# SCH_Eda_Start_2021-09-03.net
KiCad netlist of a schematic drawn in EasyEDA
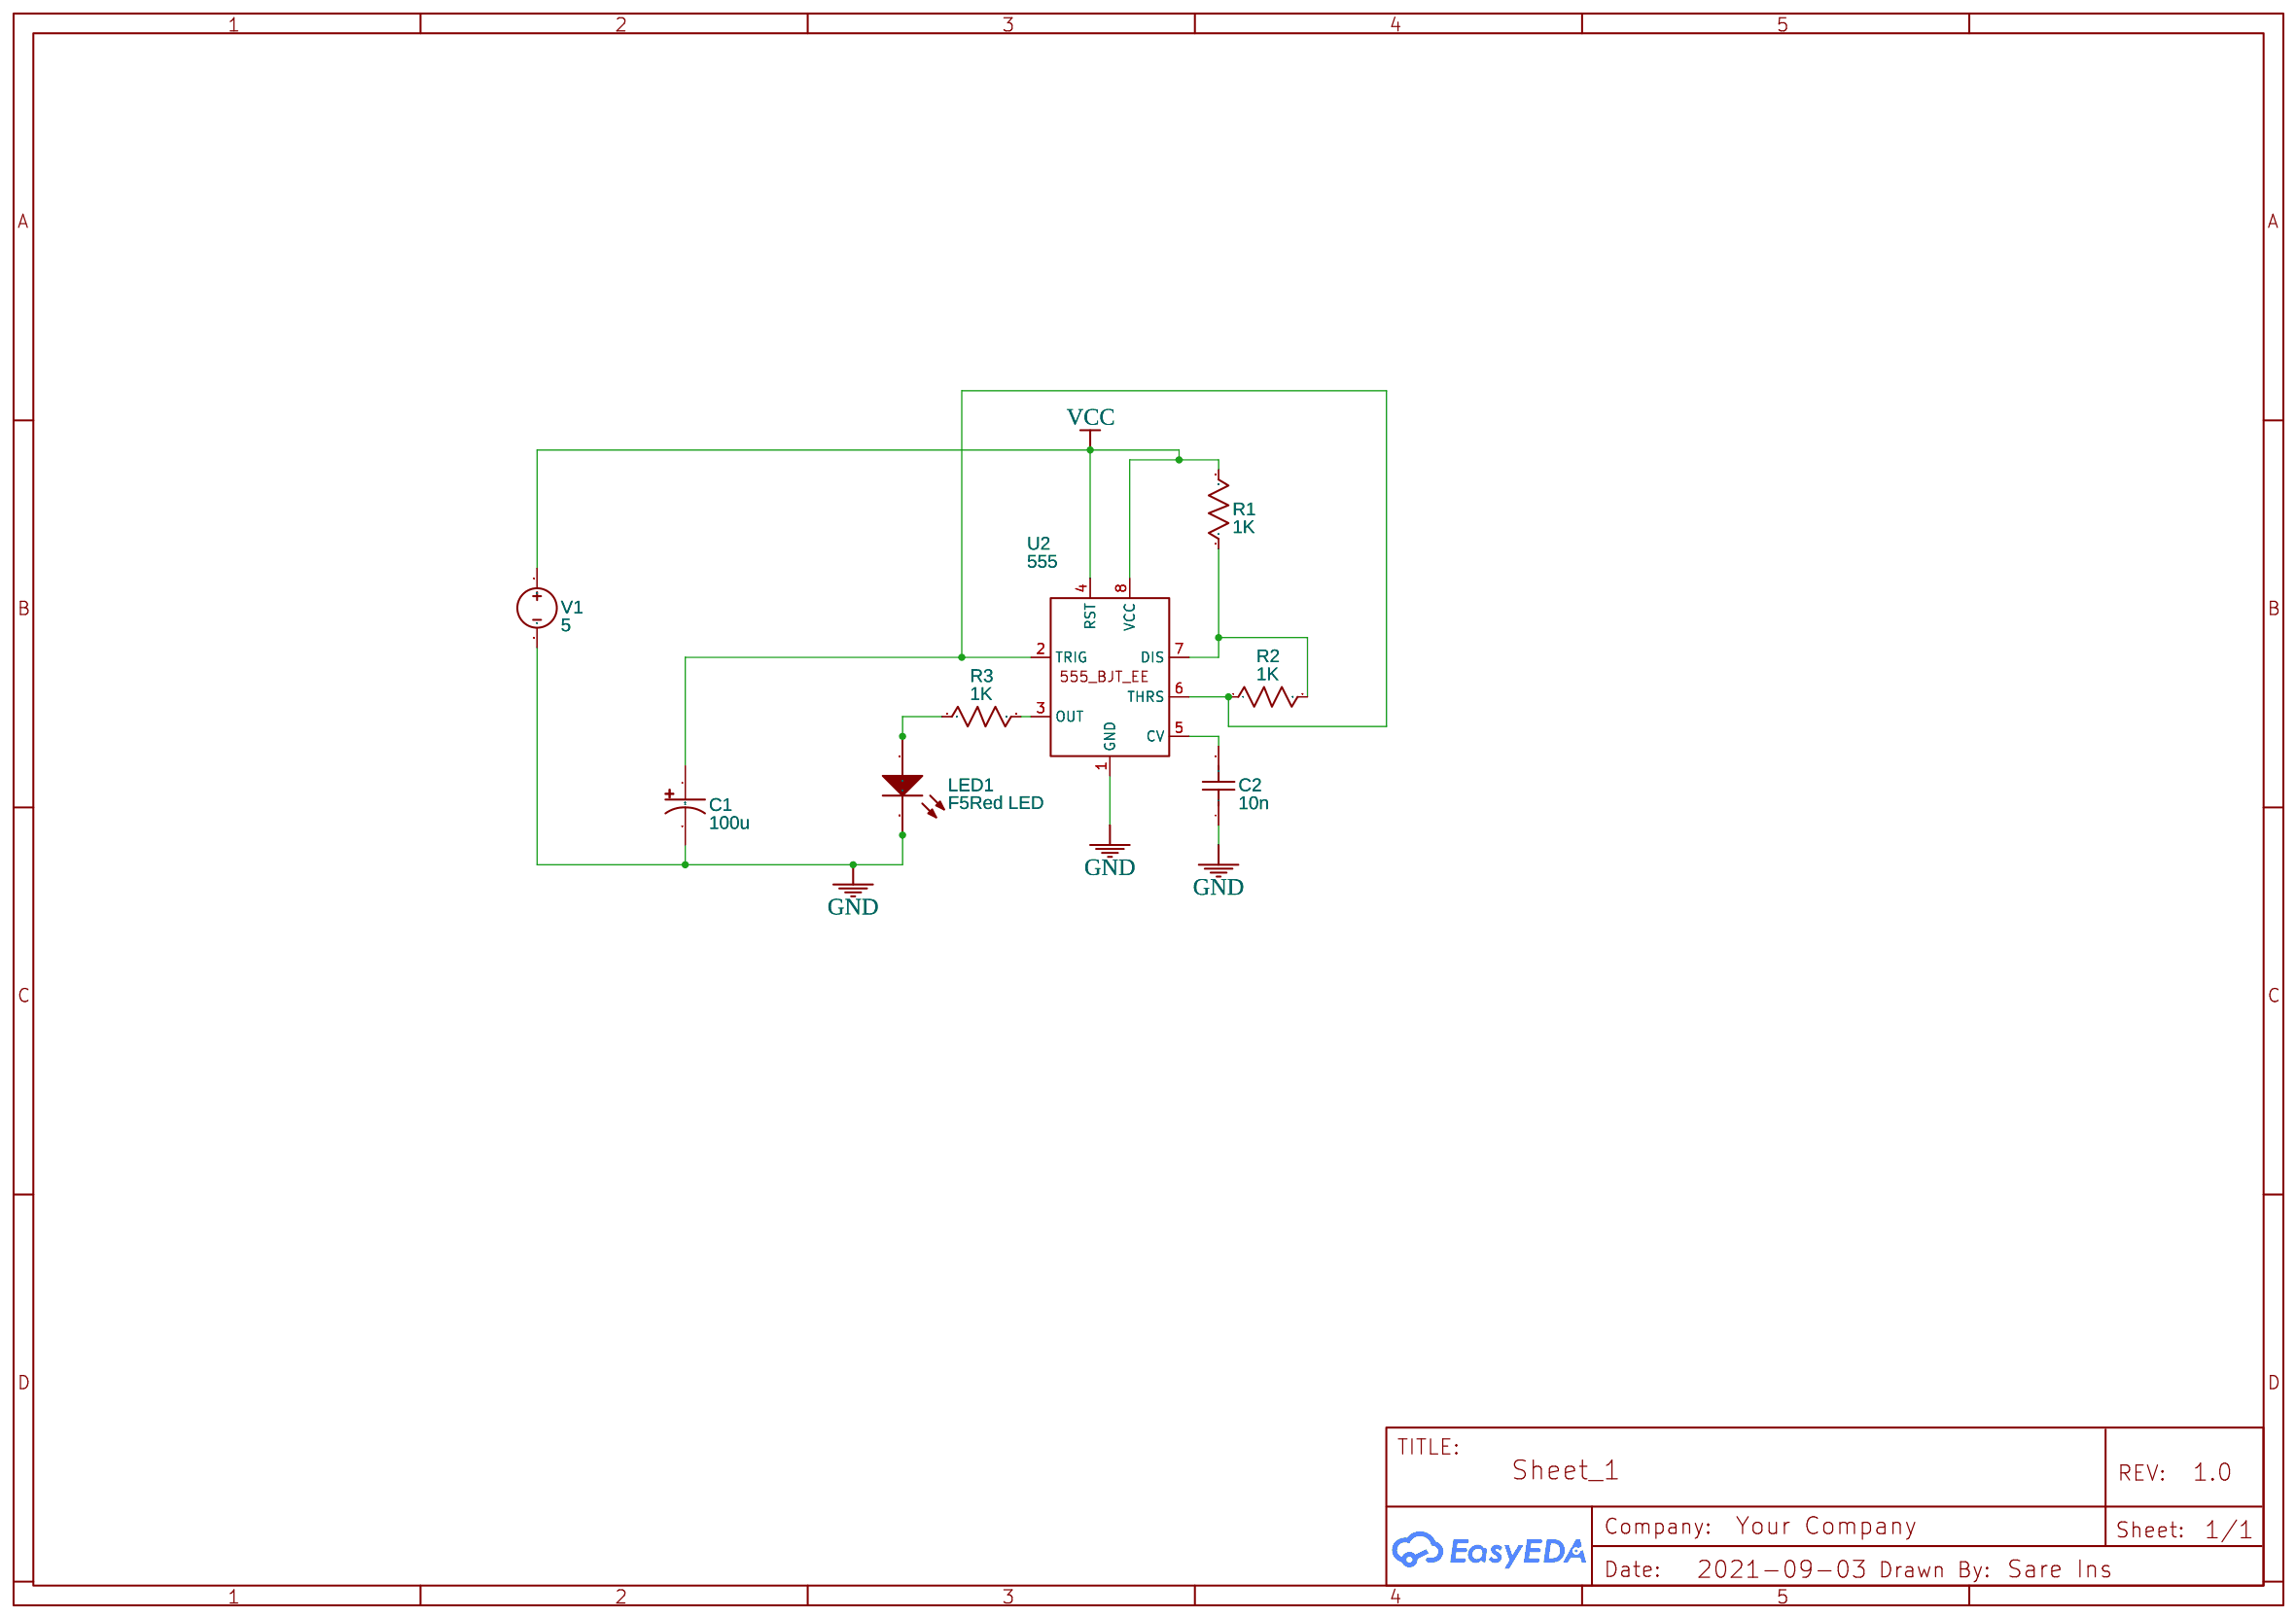
[diagram p0: schematic sheet]

(export (version "E")
  (design (tool "Eeschema 10.0.6"))
  (components
    (comp (ref "C1") (value "100u") (libsource (lib "") (part "Capacitor_Electrolytic_US")))
    (comp (ref "C2") (value "10n") (libsource (lib "") (part "Capacitor_US")))
    (comp (ref "LED1")
      (value "F5Red LED")
      (fields (field (name "BOM_Supplier Part") "C10500"))
      (libsource (lib "") (part "F5Red LED"))
    )
    (comp (ref "R1") (value "1K") (libsource (lib "") (part "Resistor_US")))
    (comp (ref "R2") (value "1K") (libsource (lib "") (part "Resistor_US_1")))
    (comp (ref "R3") (value "1K") (libsource (lib "") (part "Resistor_US_1")))
    (comp (ref "U2") (value "555") (libsource (lib "") (part "555_BJT_EE")))
    (comp (ref "V1") (value "5") (libsource (lib "") (part "VDC")))
  )
  (nets
    (net (code "1") (name "GND") (class "Default")
      (node (ref "C1") (pin "2") (pinfunction "2_2") (pintype "unspecified"))
      (node (ref "C2") (pin "1") (pinfunction "1_1") (pintype "unspecified"))
      (node (ref "LED1") (pin "1") (pinfunction "k_1") (pintype "unspecified"))
      (node (ref "LED1") (pin "2") (pinfunction "K_2") (pintype "unspecified"))
      (node (ref "U2") (pin "1") (pinfunction "GND_1") (pintype "unspecified"))
      (node (ref "V1") (pin "2") (pinfunction "2_2") (pintype "unspecified"))
    )
    (net (code "2") (name "Net-(LED1-A-Pad3)") (class "Default")
      (node (ref "LED1") (pin "3") (pinfunction "A_3") (pintype "unspecified"))
      (node (ref "LED1") (pin "4") (pinfunction "A_4") (pintype "unspecified"))
      (node (ref "R3") (pin "1") (pinfunction "1_1") (pintype "unspecified"))
    )
    (net (code "3") (name "Net-(U2-CV)") (class "Default")
      (node (ref "C2") (pin "2") (pinfunction "2_2") (pintype "unspecified"))
      (node (ref "U2") (pin "5") (pinfunction "CV_5") (pintype "unspecified"))
    )
    (net (code "4") (name "Net-(U2-DIS)") (class "Default")
      (node (ref "R1") (pin "1") (pinfunction "1_1") (pintype "unspecified"))
      (node (ref "R2") (pin "2") (pinfunction "2_2") (pintype "unspecified"))
      (node (ref "U2") (pin "7") (pinfunction "DIS_7") (pintype "unspecified"))
    )
    (net (code "5") (name "Net-(U2-OUT)") (class "Default")
      (node (ref "R3") (pin "2") (pinfunction "2_2") (pintype "unspecified"))
      (node (ref "U2") (pin "3") (pinfunction "OUT_3") (pintype "unspecified"))
    )
    (net (code "6") (name "Net-(U2-THRS)") (class "Default")
      (node (ref "C1") (pin "1") (pinfunction "1_1") (pintype "unspecified"))
      (node (ref "R2") (pin "1") (pinfunction "1_1") (pintype "unspecified"))
      (node (ref "U2") (pin "2") (pinfunction "TRIG_2") (pintype "unspecified"))
      (node (ref "U2") (pin "6") (pinfunction "THRS_6") (pintype "unspecified"))
    )
    (net (code "7") (name "VCC") (class "Default")
      (node (ref "R1") (pin "2") (pinfunction "2_2") (pintype "unspecified"))
      (node (ref "U2") (pin "4") (pinfunction "RST_4") (pintype "unspecified"))
      (node (ref "U2") (pin "8") (pinfunction "VCC_8") (pintype "unspecified"))
      (node (ref "V1") (pin "1") (pinfunction "1_1") (pintype "unspecified"))
    )
  )
)
